# Power_Supply.net
KiCad netlist of a schematic drawn in EAGLE
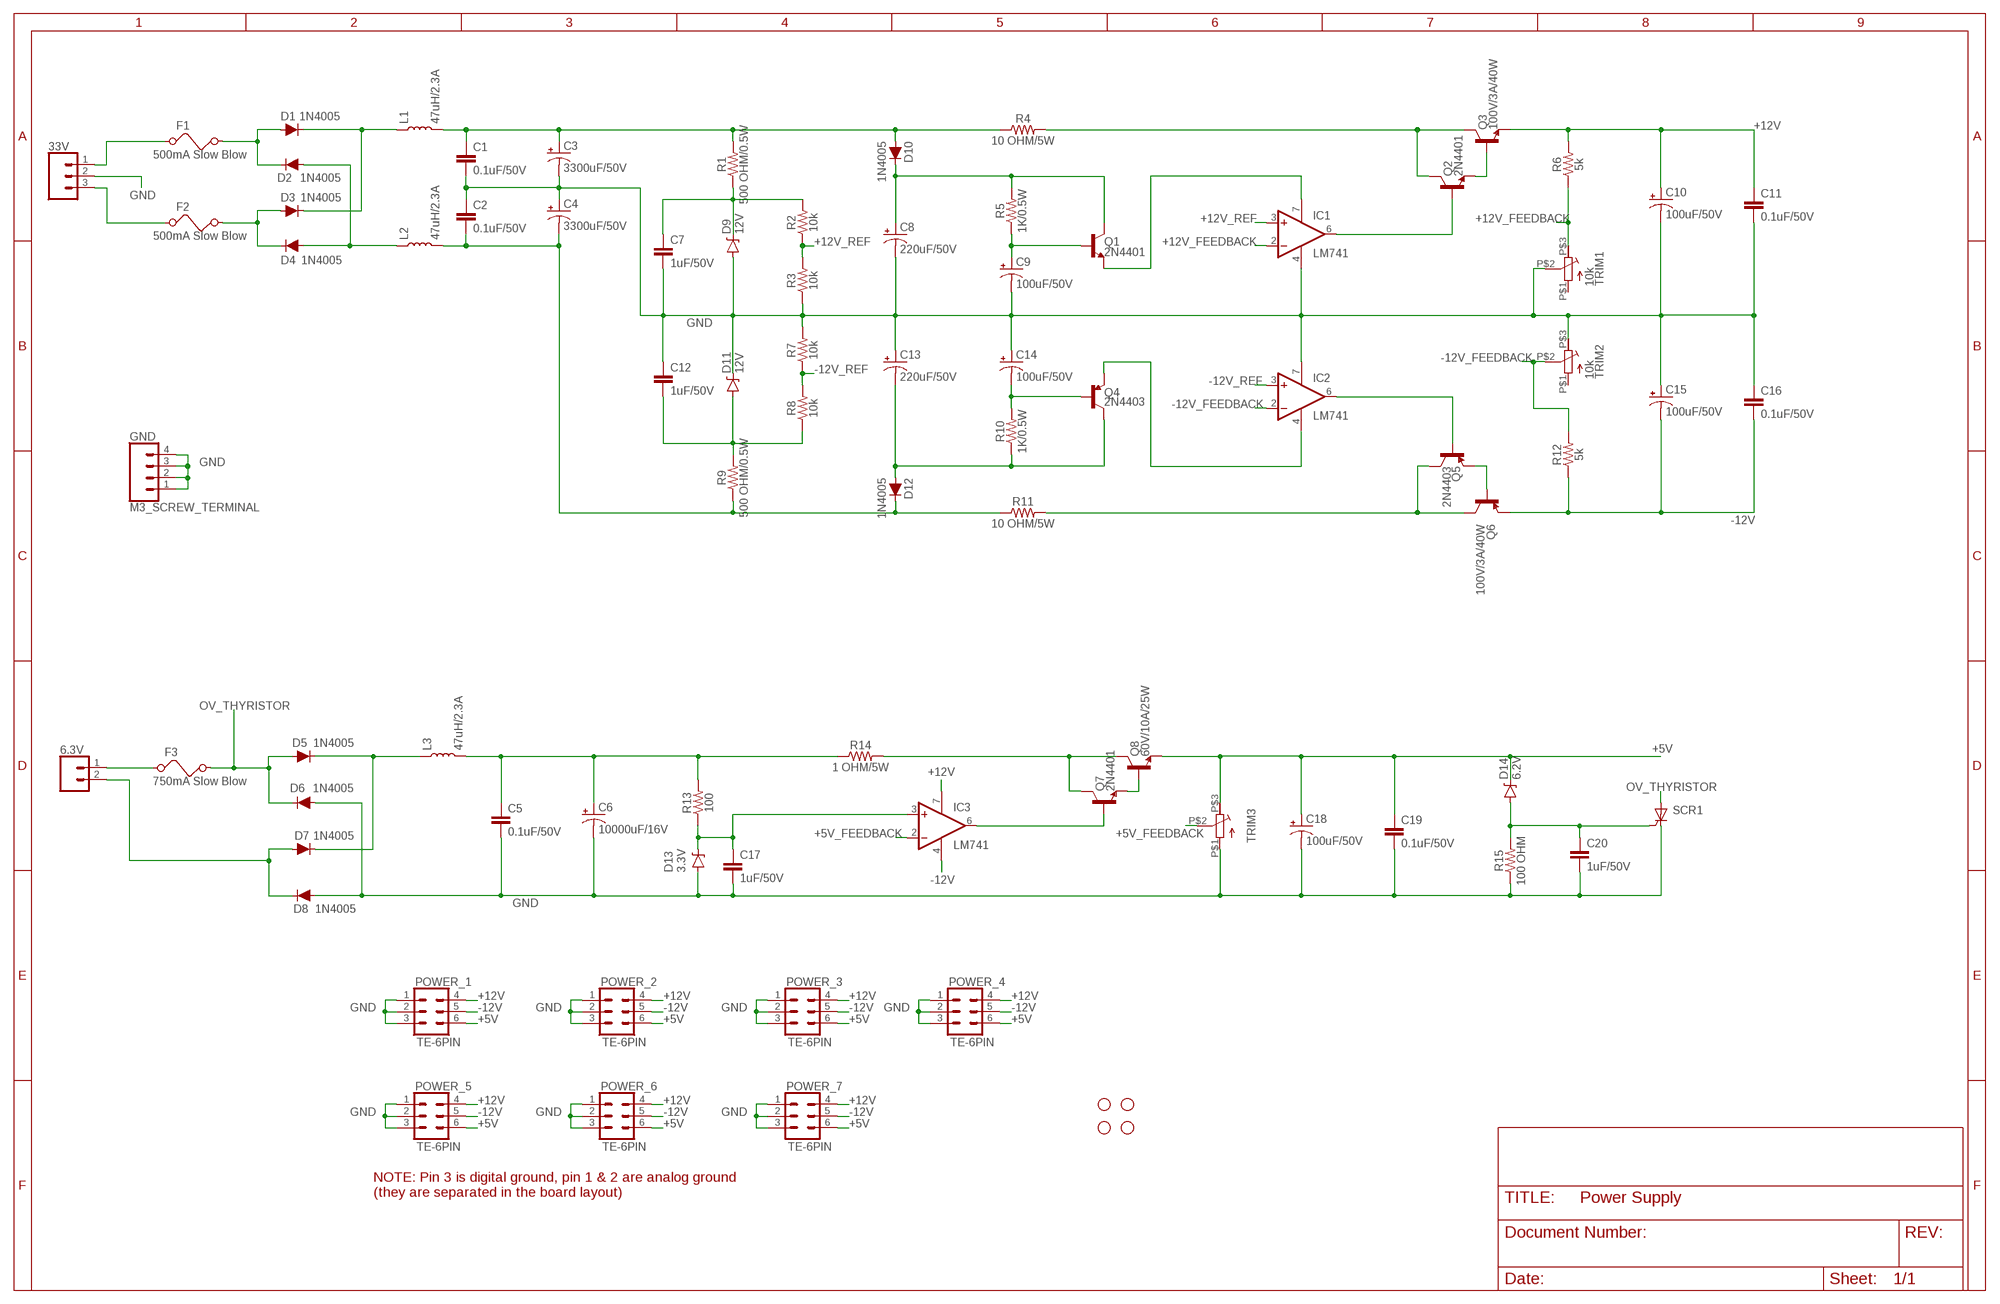
[diagram p0: schematic, sheet 1]

(export (version "E")
  (design (tool "Eeschema 10.0.6"))
  (components
    (comp (ref "6.3V")
      (value "TE-2PIN")
      (footprint "eagle-import:2_PIN_CONNECT")
      (libsource (lib "eagle-import") (part "TE-2PIN"))
    )
    (comp (ref "33V")
      (value "TE-3PIN")
      (footprint "eagle-import:3_PIN_TE")
      (libsource (lib "eagle-import") (part "TE-3PIN"))
    )
    (comp (ref "C1")
      (value "0.1uF/50V")
      (footprint "eagle-import:CERAMIC_CAPACITOR")
      (libsource (lib "eagle-import") (part "CERAMIC_CAPACITOR"))
    )
    (comp (ref "C2")
      (value "0.1uF/50V")
      (footprint "eagle-import:CERAMIC_CAPACITOR")
      (libsource (lib "eagle-import") (part "CERAMIC_CAPACITOR"))
    )
    (comp (ref "C3")
      (value "3300uF/50V")
      (footprint "eagle-import:POLARIZED_CAP_3300UF")
      (libsource (lib "eagle-import") (part "3300UF_CAP"))
    )
    (comp (ref "C4")
      (value "3300uF/50V")
      (footprint "eagle-import:POLARIZED_CAP_3300UF")
      (libsource (lib "eagle-import") (part "3300UF_CAP"))
    )
    (comp (ref "C5")
      (value "0.1uF/50V")
      (footprint "eagle-import:CERAMIC_CAPACITOR")
      (libsource (lib "eagle-import") (part "CERAMIC_CAPACITOR"))
    )
    (comp (ref "C6")
      (value "10000uF/16V")
      (footprint "eagle-import:POLARIZED_CAP_3300UF")
      (libsource (lib "eagle-import") (part "3300UF_CAP"))
    )
    (comp (ref "C7")
      (value "1uF/50V")
      (footprint "eagle-import:CERAMIC_CAPACITOR")
      (libsource (lib "eagle-import") (part "CERAMIC_CAPACITOR"))
    )
    (comp (ref "C8")
      (value "220uF/50V")
      (footprint "eagle-import:220UF_CAP")
      (libsource (lib "eagle-import") (part "220UF"))
    )
    (comp (ref "C9")
      (value "100uF/50V")
      (footprint "eagle-import:100UF_CAP")
      (libsource (lib "eagle-import") (part "100UF"))
    )
    (comp (ref "C10")
      (value "100uF/50V")
      (footprint "eagle-import:100UF_CAP")
      (libsource (lib "eagle-import") (part "100UF"))
    )
    (comp (ref "C11")
      (value "0.1uF/50V")
      (footprint "eagle-import:CERAMIC_CAPACITOR")
      (libsource (lib "eagle-import") (part "CERAMIC_CAPACITOR"))
    )
    (comp (ref "C12")
      (value "1uF/50V")
      (footprint "eagle-import:CERAMIC_CAPACITOR")
      (libsource (lib "eagle-import") (part "CERAMIC_CAPACITOR"))
    )
    (comp (ref "C13")
      (value "220uF/50V")
      (footprint "eagle-import:220UF_CAP")
      (libsource (lib "eagle-import") (part "220UF"))
    )
    (comp (ref "C14")
      (value "100uF/50V")
      (footprint "eagle-import:100UF_CAP")
      (libsource (lib "eagle-import") (part "100UF"))
    )
    (comp (ref "C15")
      (value "100uF/50V")
      (footprint "eagle-import:100UF_CAP")
      (libsource (lib "eagle-import") (part "100UF"))
    )
    (comp (ref "C16")
      (value "0.1uF/50V")
      (footprint "eagle-import:CERAMIC_CAPACITOR")
      (libsource (lib "eagle-import") (part "CERAMIC_CAPACITOR"))
    )
    (comp (ref "C17")
      (value "1uF/50V")
      (footprint "eagle-import:CERAMIC_CAPACITOR")
      (libsource (lib "eagle-import") (part "CERAMIC_CAPACITOR"))
    )
    (comp (ref "C18")
      (value "100uF/50V")
      (footprint "eagle-import:100UF_CAP")
      (libsource (lib "eagle-import") (part "100UF"))
    )
    (comp (ref "C19")
      (value "0.1uF/50V")
      (footprint "eagle-import:CERAMIC_CAPACITOR")
      (libsource (lib "eagle-import") (part "CERAMIC_CAPACITOR"))
    )
    (comp (ref "C20")
      (value "1uF/50V")
      (footprint "eagle-import:CERAMIC_CAPACITOR")
      (libsource (lib "eagle-import") (part "CERAMIC_CAPACITOR"))
    )
    (comp (ref "D1")
      (value "1N4005")
      (footprint "eagle-import:DIODE-1N4001")
      (libsource (lib "eagle-import") (part "1N4005"))
    )
    (comp (ref "D2")
      (value "1N4005")
      (footprint "eagle-import:DIODE-1N4001")
      (libsource (lib "eagle-import") (part "1N4005"))
    )
    (comp (ref "D3")
      (value "1N4005")
      (footprint "eagle-import:DIODE-1N4001")
      (libsource (lib "eagle-import") (part "1N4005"))
    )
    (comp (ref "D4")
      (value "1N4005")
      (footprint "eagle-import:DIODE-1N4001")
      (libsource (lib "eagle-import") (part "1N4005"))
    )
    (comp (ref "D5")
      (value "1N4005")
      (footprint "eagle-import:DIODE-1N4001")
      (libsource (lib "eagle-import") (part "1N4005"))
    )
    (comp (ref "D6")
      (value "1N4005")
      (footprint "eagle-import:DIODE-1N4001")
      (libsource (lib "eagle-import") (part "1N4005"))
    )
    (comp (ref "D7")
      (value "1N4005")
      (footprint "eagle-import:DIODE-1N4001")
      (libsource (lib "eagle-import") (part "1N4005"))
    )
    (comp (ref "D8")
      (value "1N4005")
      (footprint "eagle-import:DIODE-1N4001")
      (libsource (lib "eagle-import") (part "1N4005"))
    )
    (comp (ref "D9")
      (value "12V")
      (footprint "eagle-import:1W_ZENER")
      (libsource (lib "eagle-import") (part "1W_ZENER"))
    )
    (comp (ref "D10")
      (value "1N4005")
      (footprint "eagle-import:DIODE-1N4001")
      (libsource (lib "eagle-import") (part "1N4005"))
    )
    (comp (ref "D11")
      (value "12V")
      (footprint "eagle-import:1W_ZENER")
      (libsource (lib "eagle-import") (part "1W_ZENER"))
    )
    (comp (ref "D12")
      (value "1N4005")
      (footprint "eagle-import:DIODE-1N4001")
      (libsource (lib "eagle-import") (part "1N4005"))
    )
    (comp (ref "D13")
      (value "3.3V")
      (footprint "eagle-import:1W_ZENER")
      (libsource (lib "eagle-import") (part "1W_ZENER"))
    )
    (comp (ref "D14")
      (value "6.2V")
      (footprint "eagle-import:1W_ZENER")
      (libsource (lib "eagle-import") (part "1W_ZENER"))
    )
    (comp (ref "F1")
      (value "500mA Slow Blow")
      (footprint "eagle-import:FUSEHOLDER")
      (libsource (lib "eagle-import") (part "FUSE"))
    )
    (comp (ref "F2")
      (value "500mA Slow Blow")
      (footprint "eagle-import:FUSEHOLDER")
      (libsource (lib "eagle-import") (part "FUSE"))
    )
    (comp (ref "F3")
      (value "750mA Slow Blow")
      (footprint "eagle-import:FUSEHOLDER")
      (libsource (lib "eagle-import") (part "FUSE"))
    )
    (comp (ref "GND")
      (value "M3_SCREW_TERMINAL")
      (footprint "eagle-import:M3_SCREW_TERMINAL")
      (libsource (lib "eagle-import") (part "M3_SCREW_TERMINAL"))
    )
    (comp (ref "H1")
      (value "STAND-OFF")
      (footprint "eagle-import:STAND-OFF")
      (libsource (lib "eagle-import") (part "STAND-OFF"))
    )
    (comp (ref "H2")
      (value "STAND-OFF")
      (footprint "eagle-import:STAND-OFF")
      (libsource (lib "eagle-import") (part "STAND-OFF"))
    )
    (comp (ref "H3")
      (value "STAND-OFF")
      (footprint "eagle-import:STAND-OFF")
      (libsource (lib "eagle-import") (part "STAND-OFF"))
    )
    (comp (ref "H4")
      (value "STAND-OFF")
      (footprint "eagle-import:STAND-OFF")
      (libsource (lib "eagle-import") (part "STAND-OFF"))
    )
    (comp (ref "IC1")
      (value "LM741")
      (footprint "eagle-import:DIL08")
      (libsource (lib "eagle-import") (part "LM741"))
    )
    (comp (ref "IC2")
      (value "LM741")
      (footprint "eagle-import:DIL08")
      (libsource (lib "eagle-import") (part "LM741"))
    )
    (comp (ref "IC3")
      (value "LM741")
      (footprint "eagle-import:DIL08")
      (libsource (lib "eagle-import") (part "LM741"))
    )
    (comp (ref "L1")
      (value "47uH/2.3A")
      (footprint "eagle-import:47UH_2.3A_COIL")
      (libsource (lib "eagle-import") (part "47_UH_INDUCTOR"))
    )
    (comp (ref "L2")
      (value "47uH/2.3A")
      (footprint "eagle-import:47UH_2.3A_COIL")
      (libsource (lib "eagle-import") (part "47_UH_INDUCTOR"))
    )
    (comp (ref "L3")
      (value "47uH/2.3A")
      (footprint "eagle-import:47UH_2.3A_COIL")
      (libsource (lib "eagle-import") (part "47_UH_INDUCTOR"))
    )
    (comp (ref "POWER_1")
      (value "TE-6PIN")
      (footprint "eagle-import:TE_6_PIN")
      (libsource (lib "eagle-import") (part "TE-6PIN"))
    )
    (comp (ref "POWER_2")
      (value "TE-6PIN")
      (footprint "eagle-import:TE_6_PIN")
      (libsource (lib "eagle-import") (part "TE-6PIN"))
    )
    (comp (ref "POWER_3")
      (value "TE-6PIN")
      (footprint "eagle-import:TE_6_PIN")
      (libsource (lib "eagle-import") (part "TE-6PIN"))
    )
    (comp (ref "POWER_4")
      (value "TE-6PIN")
      (footprint "eagle-import:TE_6_PIN")
      (libsource (lib "eagle-import") (part "TE-6PIN"))
    )
    (comp (ref "POWER_5")
      (value "TE-6PIN")
      (footprint "eagle-import:TE_6_PIN")
      (libsource (lib "eagle-import") (part "TE-6PIN"))
    )
    (comp (ref "POWER_6")
      (value "TE-6PIN")
      (footprint "eagle-import:TE_6_PIN")
      (libsource (lib "eagle-import") (part "TE-6PIN"))
    )
    (comp (ref "POWER_7")
      (value "TE-6PIN")
      (footprint "eagle-import:TE_6_PIN")
      (libsource (lib "eagle-import") (part "TE-6PIN"))
    )
    (comp (ref "Q1")
      (value "2N4401")
      (footprint "eagle-import:TO-92")
      (libsource (lib "eagle-import") (part "2N4401"))
    )
    (comp (ref "Q2")
      (value "2N4401")
      (footprint "eagle-import:TO-92")
      (libsource (lib "eagle-import") (part "2N4401"))
    )
    (comp (ref "Q3")
      (value "100V/3A/40W")
      (footprint "eagle-import:TO-220_LARGE_HEATSINK")
      (libsource (lib "eagle-import") (part "BD241C"))
    )
    (comp (ref "Q4")
      (value "2N4403")
      (footprint "eagle-import:TO-92")
      (libsource (lib "eagle-import") (part "2N4403"))
    )
    (comp (ref "Q5")
      (value "2N4403")
      (footprint "eagle-import:TO-92")
      (libsource (lib "eagle-import") (part "2N4403"))
    )
    (comp (ref "Q6")
      (value "100V/3A/40W")
      (footprint "eagle-import:TO-220_LARGE_HEATSINK")
      (libsource (lib "eagle-import") (part "BD242C"))
    )
    (comp (ref "Q7")
      (value "2N4401")
      (footprint "eagle-import:TO-92")
      (libsource (lib "eagle-import") (part "2N4401"))
    )
    (comp (ref "Q8")
      (value "60V/10A/25W")
      (footprint "eagle-import:TO-220_SMALL_HEATSINK")
      (libsource (lib "eagle-import") (part "C6144"))
    )
    (comp (ref "R1")
      (value "500 OHM/0.5W")
      (footprint "eagle-import:0.5W_RES")
      (libsource (lib "eagle-import") (part "0.5W_RES"))
    )
    (comp (ref "R2")
      (value "10k")
      (footprint "eagle-import:0.25W_RES")
      (libsource (lib "eagle-import") (part "0.25W_RES"))
    )
    (comp (ref "R3")
      (value "10k")
      (footprint "eagle-import:0.25W_RES")
      (libsource (lib "eagle-import") (part "0.25W_RES"))
    )
    (comp (ref "R4")
      (value "10 OHM/5W")
      (footprint "eagle-import:5W_RES")
      (libsource (lib "eagle-import") (part "5W_RES"))
    )
    (comp (ref "R5")
      (value "1K/0.5W")
      (footprint "eagle-import:0.5W_RES")
      (libsource (lib "eagle-import") (part "0.5W_RES"))
    )
    (comp (ref "R6")
      (value "5k")
      (footprint "eagle-import:0.25W_RES")
      (libsource (lib "eagle-import") (part "0.25W_RES"))
    )
    (comp (ref "R7")
      (value "10k")
      (footprint "eagle-import:0.25W_RES")
      (libsource (lib "eagle-import") (part "0.25W_RES"))
    )
    (comp (ref "R8")
      (value "10k")
      (footprint "eagle-import:0.25W_RES")
      (libsource (lib "eagle-import") (part "0.25W_RES"))
    )
    (comp (ref "R9")
      (value "500 OHM/0.5W")
      (footprint "eagle-import:0.5W_RES")
      (libsource (lib "eagle-import") (part "0.5W_RES"))
    )
    (comp (ref "R10")
      (value "1K/0.5W")
      (footprint "eagle-import:0.5W_RES")
      (libsource (lib "eagle-import") (part "0.5W_RES"))
    )
    (comp (ref "R11")
      (value "10 OHM/5W")
      (footprint "eagle-import:5W_RES")
      (libsource (lib "eagle-import") (part "5W_RES"))
    )
    (comp (ref "R12")
      (value "5k")
      (footprint "eagle-import:0.25W_RES")
      (libsource (lib "eagle-import") (part "0.25W_RES"))
    )
    (comp (ref "R13")
      (value "100")
      (footprint "eagle-import:0.25W_RES")
      (libsource (lib "eagle-import") (part "0.25W_RES"))
    )
    (comp (ref "R14")
      (value "1 OHM/5W")
      (footprint "eagle-import:5W_RES")
      (libsource (lib "eagle-import") (part "5W_RES"))
    )
    (comp (ref "R15")
      (value "100 OHM")
      (footprint "eagle-import:0.25W_RES")
      (libsource (lib "eagle-import") (part "0.25W_RES"))
    )
    (comp (ref "SCR1")
      (value "THYRISTOR_4A")
      (footprint "eagle-import:TO220V")
      (libsource (lib "eagle-import") (part "THYRISTOR_4A"))
    )
    (comp (ref "TRIM1")
      (value "10k")
      (footprint "eagle-import:10K_TRIM")
      (libsource (lib "eagle-import") (part "10K_TRIMMER"))
    )
    (comp (ref "TRIM2")
      (value "10k")
      (footprint "eagle-import:10K_TRIM")
      (libsource (lib "eagle-import") (part "10K_TRIMMER"))
    )
    (comp (ref "TRIM3")
      (value "10K_TRIMMER")
      (footprint "eagle-import:10K_TRIM")
      (libsource (lib "eagle-import") (part "10K_TRIMMER"))
    )
  )
  (nets
    (net (code "1") (name "/+5V") (class "Default")
      (node (ref "C18") (pin "P1+") (pinfunction "+_P1+") (pintype "passive"))
      (node (ref "C19") (pin "P$1") (pinfunction "1_P$1") (pintype "passive"))
      (node (ref "D14") (pin "P$2CATHODE") (pinfunction "C_P$2CATHODE") (pintype "passive"))
      (node (ref "POWER_1") (pin "6") (pinfunction "6_6") (pintype "bidirectional"))
      (node (ref "POWER_2") (pin "6") (pinfunction "6_6") (pintype "bidirectional"))
      (node (ref "POWER_3") (pin "6") (pinfunction "6_6") (pintype "bidirectional"))
      (node (ref "POWER_4") (pin "6") (pinfunction "6_6") (pintype "bidirectional"))
      (node (ref "POWER_5") (pin "6") (pinfunction "6_6") (pintype "bidirectional"))
      (node (ref "POWER_6") (pin "6") (pinfunction "6_6") (pintype "bidirectional"))
      (node (ref "POWER_7") (pin "6") (pinfunction "6_6") (pintype "bidirectional"))
      (node (ref "Q8") (pin "P$3") (pinfunction "E_P$3") (pintype "passive"))
      (node (ref "TRIM3") (pin "P$3") (pinfunction "E_P$3") (pintype "passive"))
    )
    (net (code "2") (name "/+5V_FEEDBACK") (class "Default")
      (node (ref "IC3") (pin "2") (pinfunction "-IN_2") (pintype "input"))
      (node (ref "TRIM3") (pin "P$2") (pinfunction "S_P$2") (pintype "passive"))
    )
    (net (code "3") (name "/+12V") (class "Default")
      (node (ref "C10") (pin "P1+") (pinfunction "+_P1+") (pintype "passive"))
      (node (ref "C11") (pin "P$1") (pinfunction "1_P$1") (pintype "passive"))
      (node (ref "IC3") (pin "7") (pinfunction "V+_7") (pintype "power_in"))
      (node (ref "POWER_1") (pin "4") (pinfunction "2_4") (pintype "bidirectional"))
      (node (ref "POWER_2") (pin "4") (pinfunction "2_4") (pintype "bidirectional"))
      (node (ref "POWER_3") (pin "4") (pinfunction "2_4") (pintype "bidirectional"))
      (node (ref "POWER_4") (pin "4") (pinfunction "2_4") (pintype "bidirectional"))
      (node (ref "POWER_5") (pin "4") (pinfunction "2_4") (pintype "bidirectional"))
      (node (ref "POWER_6") (pin "4") (pinfunction "2_4") (pintype "bidirectional"))
      (node (ref "POWER_7") (pin "4") (pinfunction "2_4") (pintype "bidirectional"))
      (node (ref "Q3") (pin "P$3") (pinfunction "E_P$3") (pintype "passive"))
      (node (ref "R6") (pin "P$2") (pinfunction "2_P$2") (pintype "passive"))
    )
    (net (code "4") (name "/+12V_FEEDBACK") (class "Default")
      (node (ref "IC1") (pin "2") (pinfunction "-IN_2") (pintype "input"))
      (node (ref "R6") (pin "P$1") (pinfunction "1_P$1") (pintype "passive"))
      (node (ref "TRIM1") (pin "P$3") (pinfunction "E_P$3") (pintype "passive"))
    )
    (net (code "5") (name "/+12V_REF") (class "Default")
      (node (ref "IC1") (pin "3") (pinfunction "+IN_3") (pintype "input"))
      (node (ref "R2") (pin "P$1") (pinfunction "1_P$1") (pintype "passive"))
      (node (ref "R3") (pin "P$2") (pinfunction "2_P$2") (pintype "passive"))
    )
    (net (code "6") (name "/-12V") (class "Default")
      (node (ref "C15") (pin "P2-") (pinfunction "-_P2-") (pintype "passive"))
      (node (ref "C16") (pin "P$2") (pinfunction "2_P$2") (pintype "passive"))
      (node (ref "IC3") (pin "4") (pinfunction "V-_4") (pintype "power_in"))
      (node (ref "POWER_1") (pin "5") (pinfunction "4_5") (pintype "bidirectional"))
      (node (ref "POWER_2") (pin "5") (pinfunction "4_5") (pintype "bidirectional"))
      (node (ref "POWER_3") (pin "5") (pinfunction "4_5") (pintype "bidirectional"))
      (node (ref "POWER_4") (pin "5") (pinfunction "4_5") (pintype "bidirectional"))
      (node (ref "POWER_5") (pin "5") (pinfunction "4_5") (pintype "bidirectional"))
      (node (ref "POWER_6") (pin "5") (pinfunction "4_5") (pintype "bidirectional"))
      (node (ref "POWER_7") (pin "5") (pinfunction "4_5") (pintype "bidirectional"))
      (node (ref "Q6") (pin "P$3") (pinfunction "E_P$3") (pintype "passive"))
      (node (ref "R12") (pin "P$1") (pinfunction "1_P$1") (pintype "passive"))
    )
    (net (code "7") (name "/-12V_FEEDBACK") (class "Default")
      (node (ref "IC2") (pin "2") (pinfunction "-IN_2") (pintype "input"))
      (node (ref "R12") (pin "P$2") (pinfunction "2_P$2") (pintype "passive"))
      (node (ref "TRIM2") (pin "P$2") (pinfunction "S_P$2") (pintype "passive"))
    )
    (net (code "8") (name "/-12V_REF") (class "Default")
      (node (ref "IC2") (pin "3") (pinfunction "+IN_3") (pintype "input"))
      (node (ref "R7") (pin "P$1") (pinfunction "1_P$1") (pintype "passive"))
      (node (ref "R8") (pin "P$2") (pinfunction "2_P$2") (pintype "passive"))
    )
    (net (code "9") (name "/GND") (class "Default")
      (node (ref "33V") (pin "2") (pinfunction "2_2") (pintype "passive"))
      (node (ref "C1") (pin "P$2") (pinfunction "2_P$2") (pintype "passive"))
      (node (ref "C10") (pin "P2-") (pinfunction "-_P2-") (pintype "passive"))
      (node (ref "C11") (pin "P$2") (pinfunction "2_P$2") (pintype "passive"))
      (node (ref "C12") (pin "P$1") (pinfunction "1_P$1") (pintype "passive"))
      (node (ref "C13") (pin "P1+") (pinfunction "+_P1+") (pintype "passive"))
      (node (ref "C14") (pin "P1+") (pinfunction "+_P1+") (pintype "passive"))
      (node (ref "C15") (pin "P1+") (pinfunction "+_P1+") (pintype "passive"))
      (node (ref "C16") (pin "P$1") (pinfunction "1_P$1") (pintype "passive"))
      (node (ref "C17") (pin "P$2") (pinfunction "2_P$2") (pintype "passive"))
      (node (ref "C18") (pin "P2-") (pinfunction "-_P2-") (pintype "passive"))
      (node (ref "C19") (pin "P$2") (pinfunction "2_P$2") (pintype "passive"))
      (node (ref "C2") (pin "P$1") (pinfunction "1_P$1") (pintype "passive"))
      (node (ref "C20") (pin "P$2") (pinfunction "2_P$2") (pintype "passive"))
      (node (ref "C3") (pin "P2-") (pinfunction "-_P2-") (pintype "passive"))
      (node (ref "C4") (pin "P1+") (pinfunction "+_P1+") (pintype "passive"))
      (node (ref "C5") (pin "P$2") (pinfunction "2_P$2") (pintype "passive"))
      (node (ref "C6") (pin "P2-") (pinfunction "-_P2-") (pintype "passive"))
      (node (ref "C7") (pin "P$2") (pinfunction "2_P$2") (pintype "passive"))
      (node (ref "C8") (pin "P2-") (pinfunction "-_P2-") (pintype "passive"))
      (node (ref "C9") (pin "P2-") (pinfunction "-_P2-") (pintype "passive"))
      (node (ref "D11") (pin "P$2CATHODE") (pinfunction "C_P$2CATHODE") (pintype "passive"))
      (node (ref "D13") (pin "P$1ANODE") (pinfunction "A_P$1ANODE") (pintype "passive"))
      (node (ref "D6") (pin "A") (pinfunction "A_A") (pintype "passive"))
      (node (ref "D8") (pin "A") (pinfunction "A_A") (pintype "passive"))
      (node (ref "D9") (pin "P$1ANODE") (pinfunction "A_P$1ANODE") (pintype "passive"))
      (node (ref "GND") (pin "1") (pinfunction "1_1") (pintype "passive"))
      (node (ref "GND") (pin "2") (pinfunction "2_2") (pintype "passive"))
      (node (ref "GND") (pin "3") (pinfunction "3_3") (pintype "passive"))
      (node (ref "GND") (pin "4") (pinfunction "4_4") (pintype "passive"))
      (node (ref "IC1") (pin "4") (pinfunction "V-_4") (pintype "power_in"))
      (node (ref "IC2") (pin "7") (pinfunction "V+_7") (pintype "power_in"))
      (node (ref "POWER_1") (pin "1") (pinfunction "1_1") (pintype "bidirectional"))
      (node (ref "POWER_1") (pin "2") (pinfunction "3_2") (pintype "bidirectional"))
      (node (ref "POWER_1") (pin "3") (pinfunction "5_3") (pintype "bidirectional"))
      (node (ref "POWER_2") (pin "1") (pinfunction "1_1") (pintype "bidirectional"))
      (node (ref "POWER_2") (pin "2") (pinfunction "3_2") (pintype "bidirectional"))
      (node (ref "POWER_2") (pin "3") (pinfunction "5_3") (pintype "bidirectional"))
      (node (ref "POWER_3") (pin "1") (pinfunction "1_1") (pintype "bidirectional"))
      (node (ref "POWER_3") (pin "2") (pinfunction "3_2") (pintype "bidirectional"))
      (node (ref "POWER_3") (pin "3") (pinfunction "5_3") (pintype "bidirectional"))
      (node (ref "POWER_4") (pin "1") (pinfunction "1_1") (pintype "bidirectional"))
      (node (ref "POWER_4") (pin "2") (pinfunction "3_2") (pintype "bidirectional"))
      (node (ref "POWER_4") (pin "3") (pinfunction "5_3") (pintype "bidirectional"))
      (node (ref "POWER_5") (pin "1") (pinfunction "1_1") (pintype "bidirectional"))
      (node (ref "POWER_5") (pin "2") (pinfunction "3_2") (pintype "bidirectional"))
      (node (ref "POWER_5") (pin "3") (pinfunction "5_3") (pintype "bidirectional"))
      (node (ref "POWER_6") (pin "1") (pinfunction "1_1") (pintype "bidirectional"))
      (node (ref "POWER_6") (pin "2") (pinfunction "3_2") (pintype "bidirectional"))
      (node (ref "POWER_6") (pin "3") (pinfunction "5_3") (pintype "bidirectional"))
      (node (ref "POWER_7") (pin "1") (pinfunction "1_1") (pintype "bidirectional"))
      (node (ref "POWER_7") (pin "2") (pinfunction "3_2") (pintype "bidirectional"))
      (node (ref "POWER_7") (pin "3") (pinfunction "5_3") (pintype "bidirectional"))
      (node (ref "R15") (pin "P$1") (pinfunction "1_P$1") (pintype "passive"))
      (node (ref "R3") (pin "P$1") (pinfunction "1_P$1") (pintype "passive"))
      (node (ref "R7") (pin "P$2") (pinfunction "2_P$2") (pintype "passive"))
      (node (ref "SCR1") (pin "1") (pinfunction "C_1") (pintype "passive"))
      (node (ref "TRIM1") (pin "P$2") (pinfunction "S_P$2") (pintype "passive"))
      (node (ref "TRIM2") (pin "P$3") (pinfunction "E_P$3") (pintype "passive"))
      (node (ref "TRIM3") (pin "P$1") (pinfunction "A_P$1") (pintype "passive"))
    )
    (net (code "10") (name "/OV_THYRISTOR") (class "Default")
      (node (ref "D5") (pin "A") (pinfunction "A_A") (pintype "passive"))
      (node (ref "D6") (pin "C") (pinfunction "C_C") (pintype "passive"))
      (node (ref "F3") (pin "P$2") (pinfunction "2_P$2") (pintype "passive"))
      (node (ref "SCR1") (pin "2") (pinfunction "A_2") (pintype "passive"))
    )
    (net (code "11") (name "Net-(6.3V-1)") (class "Default")
      (node (ref "6.3V") (pin "2") (pinfunction "1_2") (pintype "passive"))
      (node (ref "D7") (pin "A") (pinfunction "A_A") (pintype "passive"))
      (node (ref "D8") (pin "C") (pinfunction "C_C") (pintype "passive"))
    )
    (net (code "12") (name "Net-(6.3V-2)") (class "Default")
      (node (ref "6.3V") (pin "1") (pinfunction "2_1") (pintype "passive"))
      (node (ref "F3") (pin "P$1") (pinfunction "1_P$1") (pintype "passive"))
    )
    (net (code "13") (name "Net-(33V-1)") (class "Default")
      (node (ref "33V") (pin "3") (pinfunction "1_3") (pintype "passive"))
      (node (ref "F2") (pin "P$1") (pinfunction "1_P$1") (pintype "passive"))
    )
    (net (code "14") (name "Net-(33V-3)") (class "Default")
      (node (ref "33V") (pin "1") (pinfunction "3_1") (pintype "passive"))
      (node (ref "F1") (pin "P$1") (pinfunction "1_P$1") (pintype "passive"))
    )
    (net (code "15") (name "Net-(C1-1)") (class "Default")
      (node (ref "C1") (pin "P$1") (pinfunction "1_P$1") (pintype "passive"))
      (node (ref "C3") (pin "P1+") (pinfunction "+_P1+") (pintype "passive"))
      (node (ref "D10") (pin "A") (pinfunction "A_A") (pintype "passive"))
      (node (ref "L1") (pin "P$2") (pinfunction "2_P$2") (pintype "passive"))
      (node (ref "R1") (pin "P$2") (pinfunction "2_P$2") (pintype "passive"))
      (node (ref "R4") (pin "P$1") (pinfunction "1_P$1") (pintype "passive"))
    )
    (net (code "16") (name "Net-(C2-2)") (class "Default")
      (node (ref "C2") (pin "P$2") (pinfunction "2_P$2") (pintype "passive"))
      (node (ref "C4") (pin "P2-") (pinfunction "-_P2-") (pintype "passive"))
      (node (ref "D12") (pin "C") (pinfunction "C_C") (pintype "passive"))
      (node (ref "L2") (pin "P$2") (pinfunction "2_P$2") (pintype "passive"))
      (node (ref "R11") (pin "P$1") (pinfunction "1_P$1") (pintype "passive"))
      (node (ref "R9") (pin "P$1") (pinfunction "1_P$1") (pintype "passive"))
    )
    (net (code "17") (name "Net-(C5-1)") (class "Default")
      (node (ref "C5") (pin "P$1") (pinfunction "1_P$1") (pintype "passive"))
      (node (ref "C6") (pin "P1+") (pinfunction "+_P1+") (pintype "passive"))
      (node (ref "L3") (pin "P$2") (pinfunction "2_P$2") (pintype "passive"))
      (node (ref "R13") (pin "P$2") (pinfunction "2_P$2") (pintype "passive"))
      (node (ref "R14") (pin "P$1") (pinfunction "1_P$1") (pintype "passive"))
    )
    (net (code "18") (name "Net-(C7-1)") (class "Default")
      (node (ref "C7") (pin "P$1") (pinfunction "1_P$1") (pintype "passive"))
      (node (ref "D9") (pin "P$2CATHODE") (pinfunction "C_P$2CATHODE") (pintype "passive"))
      (node (ref "R1") (pin "P$1") (pinfunction "1_P$1") (pintype "passive"))
      (node (ref "R2") (pin "P$2") (pinfunction "2_P$2") (pintype "passive"))
    )
    (net (code "19") (name "Net-(C8-+)") (class "Default")
      (node (ref "C8") (pin "P1+") (pinfunction "+_P1+") (pintype "passive"))
      (node (ref "D10") (pin "C") (pinfunction "C_C") (pintype "passive"))
      (node (ref "Q1") (pin "3") (pinfunction "C_3") (pintype "passive"))
      (node (ref "R5") (pin "P$2") (pinfunction "2_P$2") (pintype "passive"))
    )
    (net (code "20") (name "Net-(C9-+)") (class "Default")
      (node (ref "C9") (pin "P1+") (pinfunction "+_P1+") (pintype "passive"))
      (node (ref "Q1") (pin "2") (pinfunction "B_2") (pintype "passive"))
      (node (ref "R5") (pin "P$1") (pinfunction "1_P$1") (pintype "passive"))
    )
    (net (code "21") (name "Net-(C12-2)") (class "Default")
      (node (ref "C12") (pin "P$2") (pinfunction "2_P$2") (pintype "passive"))
      (node (ref "D11") (pin "P$1ANODE") (pinfunction "A_P$1ANODE") (pintype "passive"))
      (node (ref "R8") (pin "P$1") (pinfunction "1_P$1") (pintype "passive"))
      (node (ref "R9") (pin "P$2") (pinfunction "2_P$2") (pintype "passive"))
    )
    (net (code "22") (name "Net-(C13--)") (class "Default")
      (node (ref "C13") (pin "P2-") (pinfunction "-_P2-") (pintype "passive"))
      (node (ref "D12") (pin "A") (pinfunction "A_A") (pintype "passive"))
      (node (ref "Q4") (pin "3") (pinfunction "C_3") (pintype "passive"))
      (node (ref "R10") (pin "P$1") (pinfunction "1_P$1") (pintype "passive"))
    )
    (net (code "23") (name "Net-(C14--)") (class "Default")
      (node (ref "C14") (pin "P2-") (pinfunction "-_P2-") (pintype "passive"))
      (node (ref "Q4") (pin "2") (pinfunction "B_2") (pintype "passive"))
      (node (ref "R10") (pin "P$2") (pinfunction "2_P$2") (pintype "passive"))
    )
    (net (code "24") (name "Net-(C17-1)") (class "Default")
      (node (ref "C17") (pin "P$1") (pinfunction "1_P$1") (pintype "passive"))
      (node (ref "D13") (pin "P$2CATHODE") (pinfunction "C_P$2CATHODE") (pintype "passive"))
      (node (ref "IC3") (pin "3") (pinfunction "+IN_3") (pintype "input"))
      (node (ref "R13") (pin "P$1") (pinfunction "1_P$1") (pintype "passive"))
    )
    (net (code "25") (name "Net-(C20-1)") (class "Default")
      (node (ref "C20") (pin "P$1") (pinfunction "1_P$1") (pintype "passive"))
      (node (ref "D14") (pin "P$1ANODE") (pinfunction "A_P$1ANODE") (pintype "passive"))
      (node (ref "R15") (pin "P$2") (pinfunction "2_P$2") (pintype "passive"))
      (node (ref "SCR1") (pin "3") (pinfunction "G_3") (pintype "passive"))
    )
    (net (code "26") (name "Net-(F1-2)") (class "Default")
      (node (ref "D1") (pin "A") (pinfunction "A_A") (pintype "passive"))
      (node (ref "D2") (pin "C") (pinfunction "C_C") (pintype "passive"))
      (node (ref "F1") (pin "P$2") (pinfunction "2_P$2") (pintype "passive"))
    )
    (net (code "27") (name "Net-(F2-2)") (class "Default")
      (node (ref "D3") (pin "A") (pinfunction "A_A") (pintype "passive"))
      (node (ref "D4") (pin "C") (pinfunction "C_C") (pintype "passive"))
      (node (ref "F2") (pin "P$2") (pinfunction "2_P$2") (pintype "passive"))
    )
    (net (code "28") (name "Net-(IC1-OUT)") (class "Default")
      (node (ref "IC1") (pin "6") (pinfunction "OUT_6") (pintype "output"))
      (node (ref "Q2") (pin "2") (pinfunction "B_2") (pintype "passive"))
    )
    (net (code "29") (name "Net-(IC1-V+)") (class "Default")
      (node (ref "IC1") (pin "7") (pinfunction "V+_7") (pintype "power_in"))
      (node (ref "Q1") (pin "1") (pinfunction "E_1") (pintype "passive"))
    )
    (net (code "30") (name "Net-(IC2-OUT)") (class "Default")
      (node (ref "IC2") (pin "6") (pinfunction "OUT_6") (pintype "output"))
      (node (ref "Q5") (pin "2") (pinfunction "B_2") (pintype "passive"))
    )
    (net (code "31") (name "Net-(IC2-V-)") (class "Default")
      (node (ref "IC2") (pin "4") (pinfunction "V-_4") (pintype "power_in"))
      (node (ref "Q4") (pin "1") (pinfunction "E_1") (pintype "passive"))
    )
    (net (code "32") (name "Net-(IC3-OUT)") (class "Default")
      (node (ref "IC3") (pin "6") (pinfunction "OUT_6") (pintype "output"))
      (node (ref "Q7") (pin "2") (pinfunction "B_2") (pintype "passive"))
    )
    (net (code "33") (name "Net-(L1-1)") (class "Default")
      (node (ref "D1") (pin "C") (pinfunction "C_C") (pintype "passive"))
      (node (ref "D3") (pin "C") (pinfunction "C_C") (pintype "passive"))
      (node (ref "L1") (pin "P$1") (pinfunction "1_P$1") (pintype "passive"))
    )
    (net (code "34") (name "Net-(L2-1)") (class "Default")
      (node (ref "D2") (pin "A") (pinfunction "A_A") (pintype "passive"))
      (node (ref "D4") (pin "A") (pinfunction "A_A") (pintype "passive"))
      (node (ref "L2") (pin "P$1") (pinfunction "1_P$1") (pintype "passive"))
    )
    (net (code "35") (name "Net-(L3-1)") (class "Default")
      (node (ref "D5") (pin "C") (pinfunction "C_C") (pintype "passive"))
      (node (ref "D7") (pin "C") (pinfunction "C_C") (pintype "passive"))
      (node (ref "L3") (pin "P$1") (pinfunction "1_P$1") (pintype "passive"))
    )
    (net (code "36") (name "Net-(Q2-C)") (class "Default")
      (node (ref "Q2") (pin "3") (pinfunction "C_3") (pintype "passive"))
      (node (ref "Q3") (pin "P$2") (pinfunction "C_P$2") (pintype "passive"))
      (node (ref "R4") (pin "P$2") (pinfunction "2_P$2") (pintype "passive"))
    )
    (net (code "37") (name "Net-(Q2-E)") (class "Default")
      (node (ref "Q2") (pin "1") (pinfunction "E_1") (pintype "passive"))
      (node (ref "Q3") (pin "P$1") (pinfunction "B_P$1") (pintype "passive"))
    )
    (net (code "38") (name "Net-(Q5-C)") (class "Default")
      (node (ref "Q5") (pin "3") (pinfunction "C_3") (pintype "passive"))
      (node (ref "Q6") (pin "P$2") (pinfunction "C_P$2") (pintype "passive"))
      (node (ref "R11") (pin "P$2") (pinfunction "2_P$2") (pintype "passive"))
    )
    (net (code "39") (name "Net-(Q5-E)") (class "Default")
      (node (ref "Q5") (pin "1") (pinfunction "E_1") (pintype "passive"))
      (node (ref "Q6") (pin "P$1") (pinfunction "B_P$1") (pintype "passive"))
    )
    (net (code "40") (name "Net-(Q7-C)") (class "Default")
      (node (ref "Q7") (pin "3") (pinfunction "C_3") (pintype "passive"))
      (node (ref "Q8") (pin "P$2") (pinfunction "C_P$2") (pintype "passive"))
      (node (ref "R14") (pin "P$2") (pinfunction "2_P$2") (pintype "passive"))
    )
    (net (code "41") (name "Net-(Q7-E)") (class "Default")
      (node (ref "Q7") (pin "1") (pinfunction "E_1") (pintype "passive"))
      (node (ref "Q8") (pin "P$1") (pinfunction "B_P$1") (pintype "passive"))
    )
    (net (code "42") (name "unconnected-(TRIM1-A-PadP$1)") (class "Default")
      (node (ref "TRIM1") (pin "P$1") (pinfunction "A_P$1") (pintype "passive"))
    )
    (net (code "43") (name "unconnected-(TRIM2-A-PadP$1)") (class "Default")
      (node (ref "TRIM2") (pin "P$1") (pinfunction "A_P$1") (pintype "passive"))
    )
  )
)
